# KEYPAD.net
KiCad netlist of a schematic drawn in EAGLE
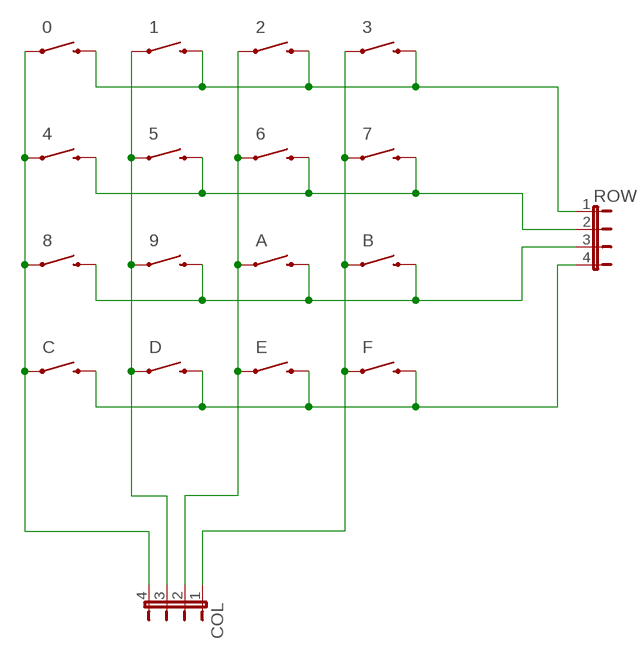
[diagram p0: schematic, sheet 1]

(export (version "E")
  (design (tool "Eeschema 10.0.6"))
  (components
    (comp (ref "0")
      (value "SWITCH-MOMENTARY-2PTH")
      (footprint "eagle-import:TACTILE-PTH")
      (libsource (lib "eagle-import") (part "SWITCH-MOMENTARY-2PTH"))
    )
    (comp (ref "1")
      (value "SWITCH-MOMENTARY-2PTH")
      (footprint "eagle-import:TACTILE-PTH")
      (libsource (lib "eagle-import") (part "SWITCH-MOMENTARY-2PTH"))
    )
    (comp (ref "2")
      (value "SWITCH-MOMENTARY-2PTH")
      (footprint "eagle-import:TACTILE-PTH")
      (libsource (lib "eagle-import") (part "SWITCH-MOMENTARY-2PTH"))
    )
    (comp (ref "3")
      (value "SWITCH-MOMENTARY-2PTH")
      (footprint "eagle-import:TACTILE-PTH")
      (libsource (lib "eagle-import") (part "SWITCH-MOMENTARY-2PTH"))
    )
    (comp (ref "4")
      (value "SWITCH-MOMENTARY-2PTH")
      (footprint "eagle-import:TACTILE-PTH")
      (libsource (lib "eagle-import") (part "SWITCH-MOMENTARY-2PTH"))
    )
    (comp (ref "5")
      (value "SWITCH-MOMENTARY-2PTH")
      (footprint "eagle-import:TACTILE-PTH")
      (libsource (lib "eagle-import") (part "SWITCH-MOMENTARY-2PTH"))
    )
    (comp (ref "6")
      (value "SWITCH-MOMENTARY-2PTH")
      (footprint "eagle-import:TACTILE-PTH")
      (libsource (lib "eagle-import") (part "SWITCH-MOMENTARY-2PTH"))
    )
    (comp (ref "7")
      (value "SWITCH-MOMENTARY-2PTH")
      (footprint "eagle-import:TACTILE-PTH")
      (libsource (lib "eagle-import") (part "SWITCH-MOMENTARY-2PTH"))
    )
    (comp (ref "8")
      (value "SWITCH-MOMENTARY-2PTH")
      (footprint "eagle-import:TACTILE-PTH")
      (libsource (lib "eagle-import") (part "SWITCH-MOMENTARY-2PTH"))
    )
    (comp (ref "9")
      (value "SWITCH-MOMENTARY-2PTH")
      (footprint "eagle-import:TACTILE-PTH")
      (libsource (lib "eagle-import") (part "SWITCH-MOMENTARY-2PTH"))
    )
    (comp (ref "A")
      (value "SWITCH-MOMENTARY-2PTH")
      (footprint "eagle-import:TACTILE-PTH")
      (libsource (lib "eagle-import") (part "SWITCH-MOMENTARY-2PTH"))
    )
    (comp (ref "B")
      (value "SWITCH-MOMENTARY-2PTH")
      (footprint "eagle-import:TACTILE-PTH")
      (libsource (lib "eagle-import") (part "SWITCH-MOMENTARY-2PTH"))
    )
    (comp (ref "C")
      (value "SWITCH-MOMENTARY-2PTH")
      (footprint "eagle-import:TACTILE-PTH")
      (libsource (lib "eagle-import") (part "SWITCH-MOMENTARY-2PTH"))
    )
    (comp (ref "COL")
      (value "JP4E")
      (footprint "eagle-import:JP4")
      (libsource (lib "eagle-import") (part "JP4E"))
    )
    (comp (ref "D")
      (value "SWITCH-MOMENTARY-2PTH")
      (footprint "eagle-import:TACTILE-PTH")
      (libsource (lib "eagle-import") (part "SWITCH-MOMENTARY-2PTH"))
    )
    (comp (ref "E")
      (value "SWITCH-MOMENTARY-2PTH")
      (footprint "eagle-import:TACTILE-PTH")
      (libsource (lib "eagle-import") (part "SWITCH-MOMENTARY-2PTH"))
    )
    (comp (ref "F")
      (value "SWITCH-MOMENTARY-2PTH")
      (footprint "eagle-import:TACTILE-PTH")
      (libsource (lib "eagle-import") (part "SWITCH-MOMENTARY-2PTH"))
    )
    (comp (ref "ROW")
      (value "JP4E")
      (footprint "eagle-import:JP4")
      (libsource (lib "eagle-import") (part "JP4E"))
    )
  )
  (nets
    (net (code "1") (name "Net-(0-2)") (class "Default")
      (node (ref "0") (pin "3") (pinfunction "2_3") (pintype "passive"))
      (node (ref "1") (pin "3") (pinfunction "2_3") (pintype "passive"))
      (node (ref "2") (pin "3") (pinfunction "2_3") (pintype "passive"))
      (node (ref "3") (pin "3") (pinfunction "2_3") (pintype "passive"))
      (node (ref "ROW") (pin "1") (pinfunction "1_1") (pintype "passive"))
    )
    (net (code "2") (name "Net-(0-Pad1)") (class "Default")
      (node (ref "0") (pin "1") (pinfunction "1_1") (pintype "passive"))
      (node (ref "4") (pin "1") (pinfunction "1_1") (pintype "passive"))
      (node (ref "8") (pin "1") (pinfunction "1_1") (pintype "passive"))
      (node (ref "C") (pin "1") (pinfunction "1_1") (pintype "passive"))
      (node (ref "COL") (pin "4") (pinfunction "4_4") (pintype "passive"))
    )
    (net (code "3") (name "Net-(1-Pad1)") (class "Default")
      (node (ref "1") (pin "1") (pinfunction "1_1") (pintype "passive"))
      (node (ref "5") (pin "1") (pinfunction "1_1") (pintype "passive"))
      (node (ref "9") (pin "1") (pinfunction "1_1") (pintype "passive"))
      (node (ref "COL") (pin "3") (pinfunction "3_3") (pintype "passive"))
      (node (ref "D") (pin "1") (pinfunction "1_1") (pintype "passive"))
    )
    (net (code "4") (name "Net-(2-Pad1)") (class "Default")
      (node (ref "2") (pin "1") (pinfunction "1_1") (pintype "passive"))
      (node (ref "6") (pin "1") (pinfunction "1_1") (pintype "passive"))
      (node (ref "A") (pin "1") (pinfunction "1_1") (pintype "passive"))
      (node (ref "COL") (pin "2") (pinfunction "2_2") (pintype "passive"))
      (node (ref "E") (pin "1") (pinfunction "1_1") (pintype "passive"))
    )
    (net (code "5") (name "Net-(3-Pad1)") (class "Default")
      (node (ref "3") (pin "1") (pinfunction "1_1") (pintype "passive"))
      (node (ref "7") (pin "1") (pinfunction "1_1") (pintype "passive"))
      (node (ref "B") (pin "1") (pinfunction "1_1") (pintype "passive"))
      (node (ref "COL") (pin "1") (pinfunction "1_1") (pintype "passive"))
      (node (ref "F") (pin "1") (pinfunction "1_1") (pintype "passive"))
    )
    (net (code "6") (name "Net-(4-2)") (class "Default")
      (node (ref "4") (pin "3") (pinfunction "2_3") (pintype "passive"))
      (node (ref "5") (pin "3") (pinfunction "2_3") (pintype "passive"))
      (node (ref "6") (pin "3") (pinfunction "2_3") (pintype "passive"))
      (node (ref "7") (pin "3") (pinfunction "2_3") (pintype "passive"))
      (node (ref "ROW") (pin "2") (pinfunction "2_2") (pintype "passive"))
    )
    (net (code "7") (name "Net-(8-2)") (class "Default")
      (node (ref "8") (pin "3") (pinfunction "2_3") (pintype "passive"))
      (node (ref "9") (pin "3") (pinfunction "2_3") (pintype "passive"))
      (node (ref "A") (pin "3") (pinfunction "2_3") (pintype "passive"))
      (node (ref "B") (pin "3") (pinfunction "2_3") (pintype "passive"))
      (node (ref "ROW") (pin "3") (pinfunction "3_3") (pintype "passive"))
    )
    (net (code "8") (name "Net-(C-2)") (class "Default")
      (node (ref "C") (pin "3") (pinfunction "2_3") (pintype "passive"))
      (node (ref "D") (pin "3") (pinfunction "2_3") (pintype "passive"))
      (node (ref "E") (pin "3") (pinfunction "2_3") (pintype "passive"))
      (node (ref "F") (pin "3") (pinfunction "2_3") (pintype "passive"))
      (node (ref "ROW") (pin "4") (pinfunction "4_4") (pintype "passive"))
    )
  )
)
